# ADSR.net
KiCad netlist of a schematic drawn in EAGLE
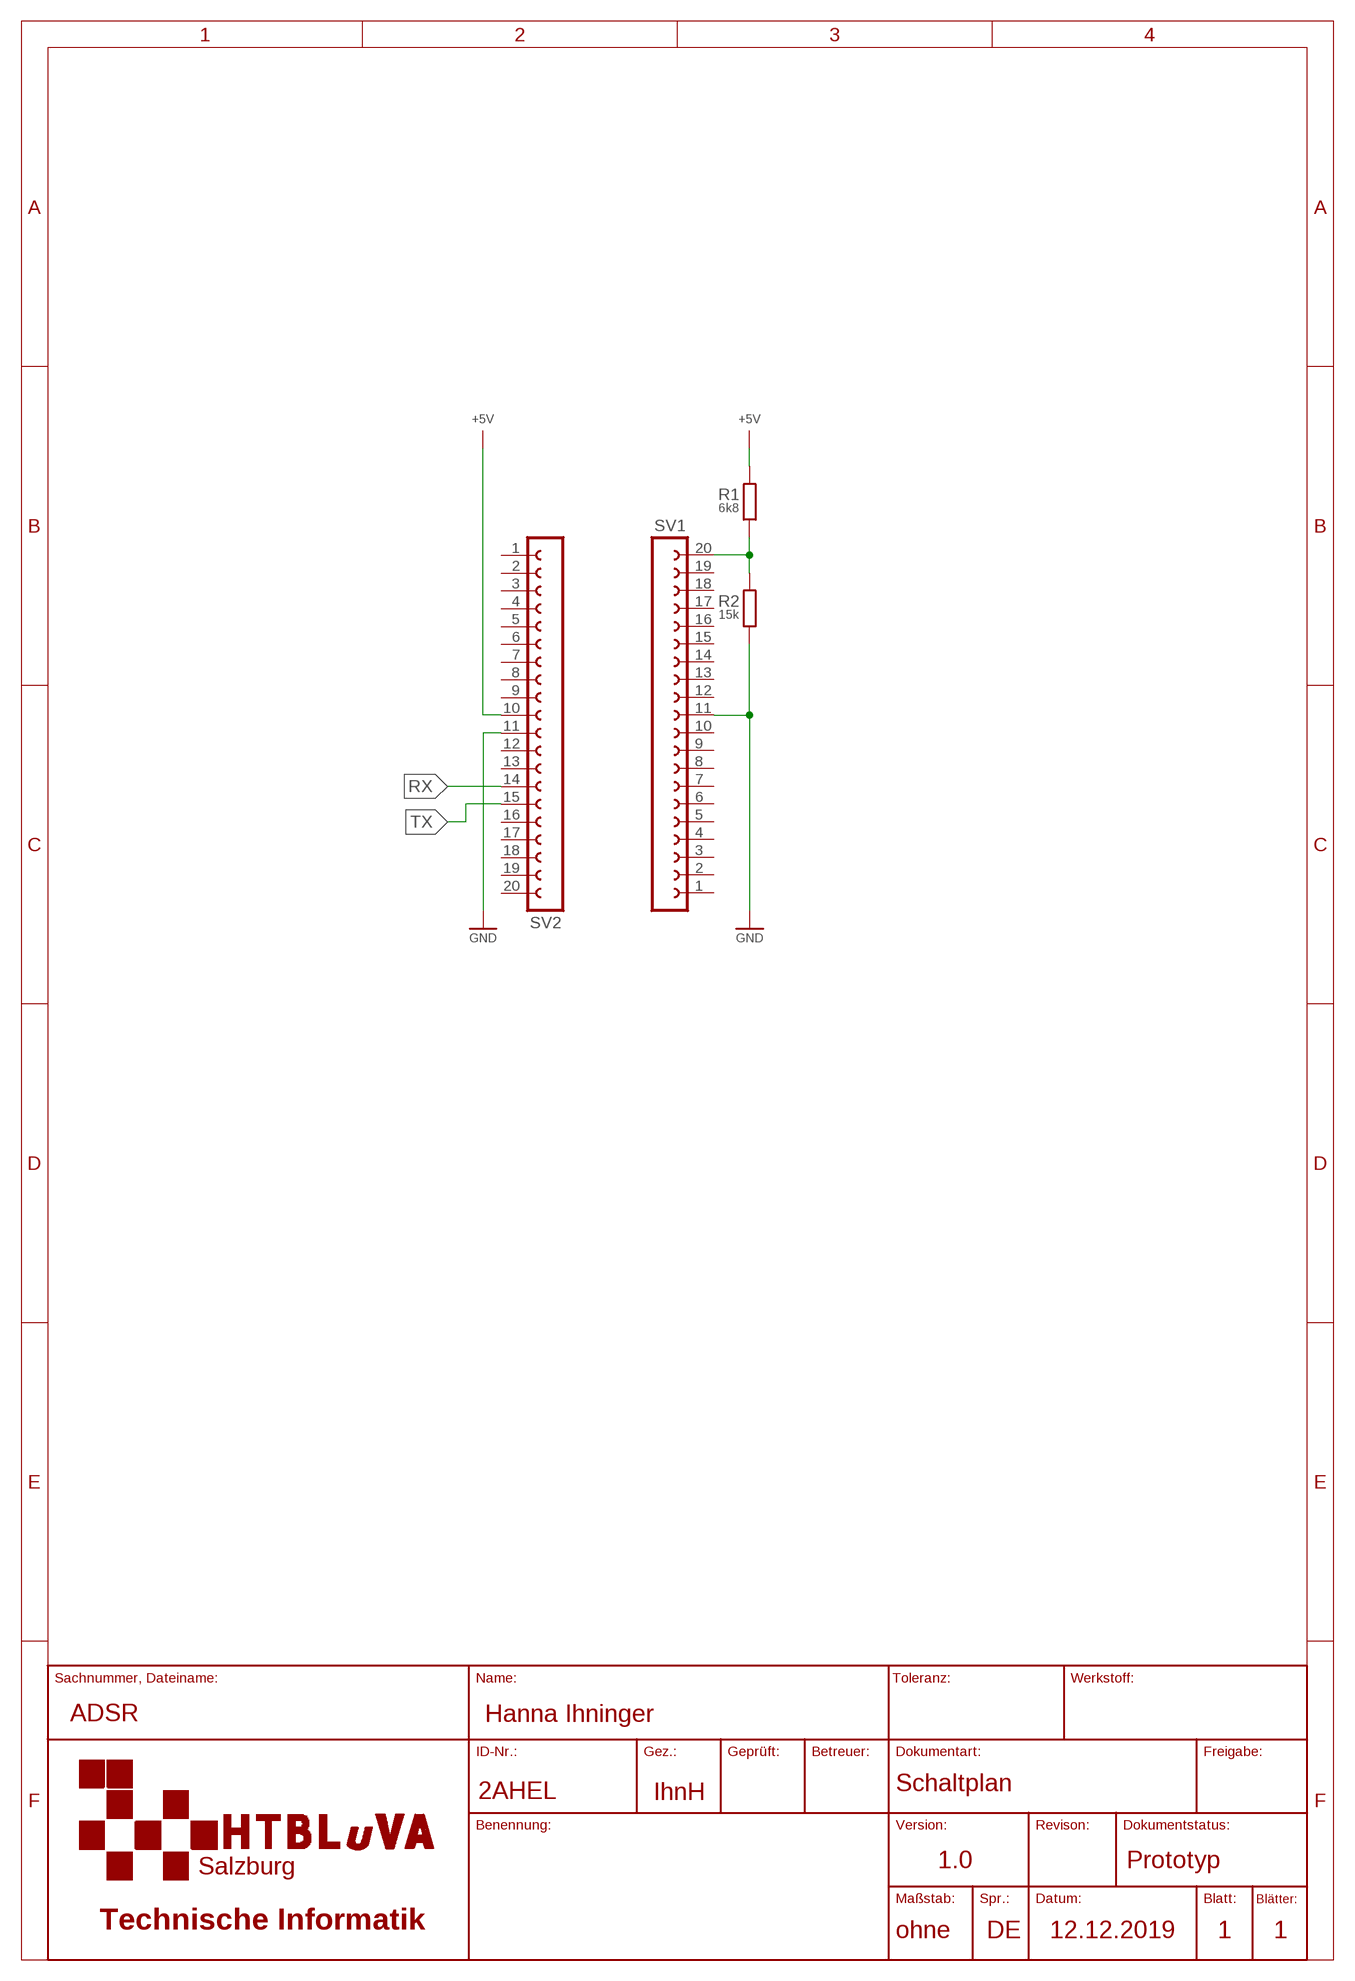
[diagram p0: schematic, sheet 1]

(export (version "E")
  (design (tool "Eeschema 10.0.6"))
  (components
    (comp (ref "R1")
      (value "6k8")
      (footprint "eagle-import:R1206")
      (libsource (lib "eagle-import") (part "R-EUSR1206"))
    )
    (comp (ref "R2")
      (value "15k")
      (footprint "eagle-import:R1206")
      (libsource (lib "eagle-import") (part "R-EUSR1206"))
    )
    (comp (ref "SV1")
      (value "FE20-1")
      (footprint "eagle-import:FE20")
      (libsource (lib "eagle-import") (part "FE20-1"))
    )
    (comp (ref "SV2")
      (value "FE20-1")
      (footprint "eagle-import:FE20")
      (libsource (lib "eagle-import") (part "FE20-1"))
    )
  )
  (nets
    (net (code "1") (name "+5V") (class "Default")
      (node (ref "R1") (pin "2") (pinfunction "2_2") (pintype "passive"))
      (node (ref "SV2") (pin "10") (pinfunction "10_10") (pintype "passive"))
    )
    (net (code "2") (name "GND") (class "Default")
      (node (ref "R2") (pin "1") (pinfunction "1_1") (pintype "passive"))
      (node (ref "SV1") (pin "11") (pinfunction "11_11") (pintype "passive"))
      (node (ref "SV2") (pin "11") (pinfunction "11_11") (pintype "passive"))
    )
    (net (code "3") (name "Net-(R1-Pad1)") (class "Default")
      (node (ref "R1") (pin "1") (pinfunction "1_1") (pintype "passive"))
      (node (ref "R2") (pin "2") (pinfunction "2_2") (pintype "passive"))
      (node (ref "SV1") (pin "20") (pinfunction "20_20") (pintype "passive"))
    )
    (net (code "4") (name "RX") (class "Default")
      (node (ref "SV2") (pin "14") (pinfunction "14_14") (pintype "passive"))
    )
    (net (code "5") (name "TX") (class "Default")
      (node (ref "SV2") (pin "15") (pinfunction "15_15") (pintype "passive"))
    )
    (net (code "6") (name "unconnected-(SV1-Pad1)") (class "Default")
      (node (ref "SV1") (pin "1") (pinfunction "1_1") (pintype "passive"))
    )
    (net (code "7") (name "unconnected-(SV1-Pad2)") (class "Default")
      (node (ref "SV1") (pin "2") (pinfunction "2_2") (pintype "passive"))
    )
    (net (code "8") (name "unconnected-(SV1-Pad3)") (class "Default")
      (node (ref "SV1") (pin "3") (pinfunction "3_3") (pintype "passive"))
    )
    (net (code "9") (name "unconnected-(SV1-Pad4)") (class "Default")
      (node (ref "SV1") (pin "4") (pinfunction "4_4") (pintype "passive"))
    )
    (net (code "10") (name "unconnected-(SV1-Pad5)") (class "Default")
      (node (ref "SV1") (pin "5") (pinfunction "5_5") (pintype "passive"))
    )
    (net (code "11") (name "unconnected-(SV1-Pad6)") (class "Default")
      (node (ref "SV1") (pin "6") (pinfunction "6_6") (pintype "passive"))
    )
    (net (code "12") (name "unconnected-(SV1-Pad7)") (class "Default")
      (node (ref "SV1") (pin "7") (pinfunction "7_7") (pintype "passive"))
    )
    (net (code "13") (name "unconnected-(SV1-Pad8)") (class "Default")
      (node (ref "SV1") (pin "8") (pinfunction "8_8") (pintype "passive"))
    )
    (net (code "14") (name "unconnected-(SV1-Pad9)") (class "Default")
      (node (ref "SV1") (pin "9") (pinfunction "9_9") (pintype "passive"))
    )
    (net (code "15") (name "unconnected-(SV1-Pad10)") (class "Default")
      (node (ref "SV1") (pin "10") (pinfunction "10_10") (pintype "passive"))
    )
    (net (code "16") (name "unconnected-(SV1-Pad12)") (class "Default")
      (node (ref "SV1") (pin "12") (pinfunction "12_12") (pintype "passive"))
    )
    (net (code "17") (name "unconnected-(SV1-Pad13)") (class "Default")
      (node (ref "SV1") (pin "13") (pinfunction "13_13") (pintype "passive"))
    )
    (net (code "18") (name "unconnected-(SV1-Pad14)") (class "Default")
      (node (ref "SV1") (pin "14") (pinfunction "14_14") (pintype "passive"))
    )
    (net (code "19") (name "unconnected-(SV1-Pad15)") (class "Default")
      (node (ref "SV1") (pin "15") (pinfunction "15_15") (pintype "passive"))
    )
    (net (code "20") (name "unconnected-(SV1-Pad16)") (class "Default")
      (node (ref "SV1") (pin "16") (pinfunction "16_16") (pintype "passive"))
    )
    (net (code "21") (name "unconnected-(SV1-Pad17)") (class "Default")
      (node (ref "SV1") (pin "17") (pinfunction "17_17") (pintype "passive"))
    )
    (net (code "22") (name "unconnected-(SV1-Pad18)") (class "Default")
      (node (ref "SV1") (pin "18") (pinfunction "18_18") (pintype "passive"))
    )
    (net (code "23") (name "unconnected-(SV1-Pad19)") (class "Default")
      (node (ref "SV1") (pin "19") (pinfunction "19_19") (pintype "passive"))
    )
    (net (code "24") (name "unconnected-(SV2-Pad1)") (class "Default")
      (node (ref "SV2") (pin "1") (pinfunction "1_1") (pintype "passive"))
    )
    (net (code "25") (name "unconnected-(SV2-Pad2)") (class "Default")
      (node (ref "SV2") (pin "2") (pinfunction "2_2") (pintype "passive"))
    )
    (net (code "26") (name "unconnected-(SV2-Pad3)") (class "Default")
      (node (ref "SV2") (pin "3") (pinfunction "3_3") (pintype "passive"))
    )
    (net (code "27") (name "unconnected-(SV2-Pad4)") (class "Default")
      (node (ref "SV2") (pin "4") (pinfunction "4_4") (pintype "passive"))
    )
    (net (code "28") (name "unconnected-(SV2-Pad5)") (class "Default")
      (node (ref "SV2") (pin "5") (pinfunction "5_5") (pintype "passive"))
    )
    (net (code "29") (name "unconnected-(SV2-Pad6)") (class "Default")
      (node (ref "SV2") (pin "6") (pinfunction "6_6") (pintype "passive"))
    )
    (net (code "30") (name "unconnected-(SV2-Pad7)") (class "Default")
      (node (ref "SV2") (pin "7") (pinfunction "7_7") (pintype "passive"))
    )
    (net (code "31") (name "unconnected-(SV2-Pad8)") (class "Default")
      (node (ref "SV2") (pin "8") (pinfunction "8_8") (pintype "passive"))
    )
    (net (code "32") (name "unconnected-(SV2-Pad9)") (class "Default")
      (node (ref "SV2") (pin "9") (pinfunction "9_9") (pintype "passive"))
    )
    (net (code "33") (name "unconnected-(SV2-Pad12)") (class "Default")
      (node (ref "SV2") (pin "12") (pinfunction "12_12") (pintype "passive"))
    )
    (net (code "34") (name "unconnected-(SV2-Pad13)") (class "Default")
      (node (ref "SV2") (pin "13") (pinfunction "13_13") (pintype "passive"))
    )
    (net (code "35") (name "unconnected-(SV2-Pad16)") (class "Default")
      (node (ref "SV2") (pin "16") (pinfunction "16_16") (pintype "passive"))
    )
    (net (code "36") (name "unconnected-(SV2-Pad17)") (class "Default")
      (node (ref "SV2") (pin "17") (pinfunction "17_17") (pintype "passive"))
    )
    (net (code "37") (name "unconnected-(SV2-Pad18)") (class "Default")
      (node (ref "SV2") (pin "18") (pinfunction "18_18") (pintype "passive"))
    )
    (net (code "38") (name "unconnected-(SV2-Pad19)") (class "Default")
      (node (ref "SV2") (pin "19") (pinfunction "19_19") (pintype "passive"))
    )
    (net (code "39") (name "unconnected-(SV2-Pad20)") (class "Default")
      (node (ref "SV2") (pin "20") (pinfunction "20_20") (pintype "passive"))
    )
  )
)
